# current.net
KiCad netlist of a schematic drawn in EAGLE
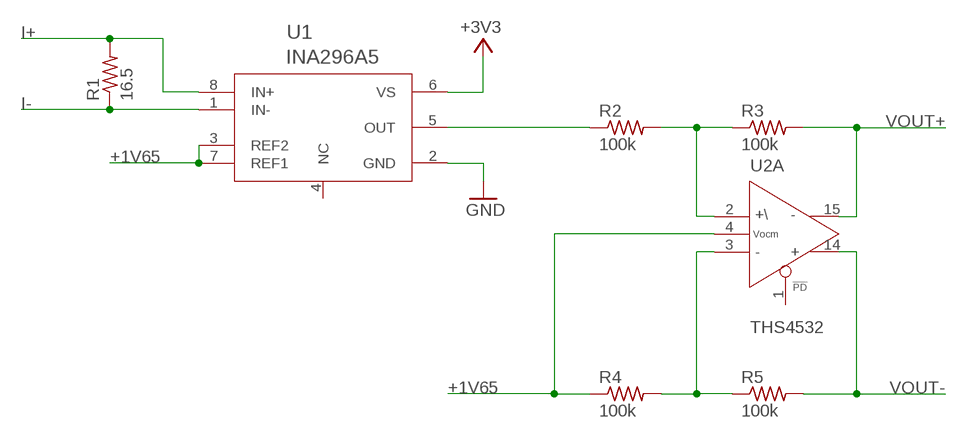
[diagram p0: schematic, sheet 1]

(export (version "E")
  (design (tool "Eeschema 10.0.6"))
  (components
    (comp (ref "R1")
      (value "16.5")
      (footprint "eagle-import:R0805")
      (libsource (lib "eagle-import") (part "R-US_R0805"))
    )
    (comp (ref "R2")
      (value "100k")
      (footprint "eagle-import:R0805")
      (libsource (lib "eagle-import") (part "R-US_R0805"))
    )
    (comp (ref "R3")
      (value "100k")
      (footprint "eagle-import:R0805")
      (libsource (lib "eagle-import") (part "R-US_R0805"))
    )
    (comp (ref "R4")
      (value "100k")
      (footprint "eagle-import:R0805")
      (libsource (lib "eagle-import") (part "R-US_R0805"))
    )
    (comp (ref "R5")
      (value "100k")
      (footprint "eagle-import:R0805")
      (libsource (lib "eagle-import") (part "R-US_R0805"))
    )
    (comp (ref "U1")
      (value "INA296A5")
      (footprint "eagle-import:SOT65P280X110-8N")
      (fields (field (name "MPN") "INA296A5IDDFR") (field (name "AUTHOR") "John Madden <jmadden173@pm.me>"))
      (libsource (lib "eagle-import") (part "INA296A5"))
    )
    (comp (ref "U2")
      (value "THS4532")
      (footprint "eagle-import:SOP65P640X120-16N")
      (fields (field (name "MPN") "THS4532IPW") (field (name "AUTHOR") "John Madden <jmadden173@pm.me>"))
      (libsource (lib "eagle-import") (part "THS4532"))
    )
  )
  (nets
    (net (code "1") (name "+3V3") (class "Default")
      (node (ref "U1") (pin "6") (pinfunction "VS_6") (pintype "power_in"))
    )
    (net (code "2") (name "/+1V65") (class "Default")
      (node (ref "R4") (pin "1") (pinfunction "1_1") (pintype "passive"))
      (node (ref "U1") (pin "3") (pinfunction "REF2_3") (pintype "bidirectional"))
      (node (ref "U1") (pin "7") (pinfunction "REF1_7") (pintype "bidirectional"))
      (node (ref "U2") (pin "4") (pinfunction "VOCM_4") (pintype "input"))
    )
    (net (code "3") (name "/I+") (class "Default")
      (node (ref "R1") (pin "2") (pinfunction "2_2") (pintype "passive"))
      (node (ref "U1") (pin "8") (pinfunction "IN+_8") (pintype "input"))
    )
    (net (code "4") (name "/I-") (class "Default")
      (node (ref "R1") (pin "1") (pinfunction "1_1") (pintype "passive"))
      (node (ref "U1") (pin "1") (pinfunction "IN-_1") (pintype "input"))
    )
    (net (code "5") (name "/VOUT+") (class "Default")
      (node (ref "R3") (pin "2") (pinfunction "2_2") (pintype "passive"))
      (node (ref "U2") (pin "15") (pinfunction "OUT-_15") (pintype "output"))
    )
    (net (code "6") (name "/VOUT-") (class "Default")
      (node (ref "R5") (pin "2") (pinfunction "2_2") (pintype "passive"))
      (node (ref "U2") (pin "14") (pinfunction "OUT+_14") (pintype "output"))
    )
    (net (code "7") (name "GND") (class "Default")
      (node (ref "U1") (pin "2") (pinfunction "GND_2") (pintype "power_in"))
    )
    (net (code "8") (name "Net-(U1-OUT)") (class "Default")
      (node (ref "R2") (pin "1") (pinfunction "1_1") (pintype "passive"))
      (node (ref "U1") (pin "5") (pinfunction "OUT_5") (pintype "output"))
    )
    (net (code "9") (name "Net-(U2A-+IN)") (class "Default")
      (node (ref "R2") (pin "2") (pinfunction "2_2") (pintype "passive"))
      (node (ref "R3") (pin "1") (pinfunction "1_1") (pintype "passive"))
      (node (ref "U2") (pin "2") (pinfunction "+IN_2") (pintype "input"))
    )
    (net (code "10") (name "Net-(U2A--IN)") (class "Default")
      (node (ref "R4") (pin "2") (pinfunction "2_2") (pintype "passive"))
      (node (ref "R5") (pin "1") (pinfunction "1_1") (pintype "passive"))
      (node (ref "U2") (pin "3") (pinfunction "-IN_3") (pintype "input"))
    )
    (net (code "11") (name "unconnected-(U1-NC-Pad4)") (class "Default")
      (node (ref "U1") (pin "4") (pinfunction "NC_4") (pintype "no_connect"))
    )
    (net (code "12") (name "unconnected-(U2A-~{PD}-Pad1)") (class "Default")
      (node (ref "U2") (pin "1") (pinfunction "~{PD}_1") (pintype "input"))
    )
  )
)
